# Flow_sensor.net
KiCad netlist of a schematic drawn in Altium Designer
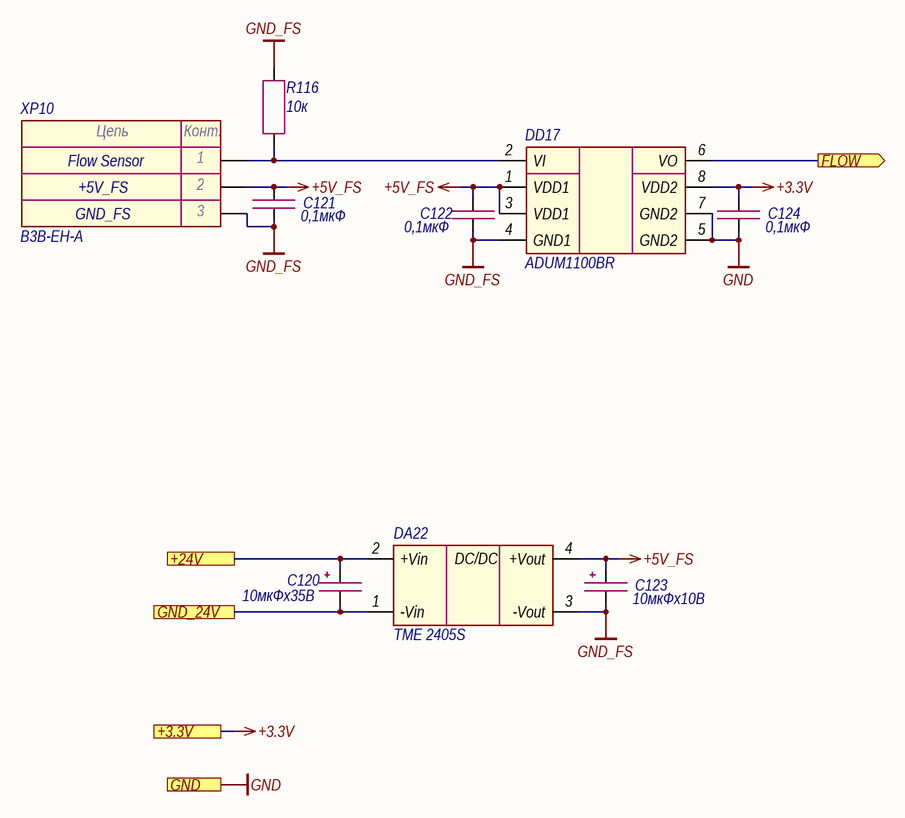
[diagram p0: Flow_sensor.SchDoc]

(export (version "E")
  (design (tool "Eeschema 10.0.6"))
  (components
    (comp (ref "C120")
      (value "10мкФх35B")
      (footprint "Pcb_library:CAP_C")
      (libsource (lib "Schem_library") (part "Capacitor_Polar"))
    )
    (comp (ref "C121")
      (value "0,1мкФ")
      (footprint "Pcb_library:CAP_0603")
      (fields (field (name "MANUFACTURER") "Murata"))
      (libsource (lib "Schem_library") (part "Capacitor"))
    )
    (comp (ref "C122")
      (value "0,1мкФ")
      (footprint "Pcb_library:CAP_0603")
      (fields (field (name "MANUFACTURER") "Murata"))
      (libsource (lib "Schem_library") (part "Capacitor"))
    )
    (comp (ref "C123")
      (value "10мкФх10B")
      (footprint "Pcb_library:CAP_A")
      (libsource (lib "Schem_library") (part "Capacitor_Polar"))
    )
    (comp (ref "C124")
      (value "0,1мкФ")
      (footprint "Pcb_library:CAP_0603")
      (fields (field (name "MANUFACTURER") "Murata"))
      (libsource (lib "Schem_library") (part "Capacitor"))
    )
    (comp (ref "DA22")
      (value "TME 2405S")
      (footprint "Pcb_library:TME (SIP-4)")
      (fields (field (name "MANUFACTURER") "Traco Power"))
      (libsource (lib "Schem_library") (part "TME"))
    )
    (comp (ref "DD17")
      (value "ADUM1100BR")
      (footprint "Pcb_library:SOIC-8")
      (fields (field (name "MANUFACTURER") "Analog Devices"))
      (libsource (lib "Schem_library") (part "ADUM1100"))
    )
    (comp (ref "R116")
      (value "10к")
      (footprint "Pcb_library:RES_0603")
      (fields (field (name "MANUFACTURER") "Yageo"))
      (libsource (lib "Schem_library") (part "Resistor"))
    )
    (comp (ref "XP10")
      (value "B3B-EH-A")
      (footprint "B3B-EH-A")
      (fields (field (name "MANUFACTURER") "JST"))
      (libsource (lib "Schem_library") (part "Connector-3"))
    )
  )
  (nets
    (net (code "1") (name "+3.3V") (class "Default")
      (node (ref "C124") (pin "1") (pinfunction "1_1") (pintype "passive"))
      (node (ref "DD17") (pin "8") (pinfunction "VDD2_8") (pintype "passive"))
    )
    (net (code "2") (name "+5V_FS") (class "Default")
      (node (ref "C121") (pin "1") (pinfunction "1_1") (pintype "passive"))
      (node (ref "C122") (pin "1") (pinfunction "1_1") (pintype "passive"))
      (node (ref "C123") (pin "1") (pinfunction "1_1") (pintype "passive"))
      (node (ref "DA22") (pin "4") (pinfunction "+Vout_4") (pintype "passive"))
      (node (ref "DD17") (pin "1") (pinfunction "VDD1_1") (pintype "passive"))
      (node (ref "DD17") (pin "3") (pinfunction "VDD1_3") (pintype "passive"))
      (node (ref "XP10") (pin "2") (pintype "passive"))
    )
    (net (code "3") (name "/+24V") (class "Default")
      (node (ref "C120") (pin "1") (pinfunction "1_1") (pintype "passive"))
      (node (ref "DA22") (pin "2") (pinfunction "+Vin_2") (pintype "passive"))
    )
    (net (code "4") (name "/FLOW") (class "Default")
      (node (ref "DD17") (pin "6") (pinfunction "VO_6") (pintype "passive"))
    )
    (net (code "5") (name "/GND_24V") (class "Default")
      (node (ref "C120") (pin "2") (pinfunction "2_2") (pintype "passive"))
      (node (ref "DA22") (pin "1") (pinfunction "-Vin_1") (pintype "passive"))
    )
    (net (code "6") (name "GND") (class "Default")
      (node (ref "C124") (pin "2") (pinfunction "2_2") (pintype "passive"))
      (node (ref "DD17") (pin "5") (pinfunction "GND2_5") (pintype "passive"))
      (node (ref "DD17") (pin "7") (pinfunction "GND2_7") (pintype "passive"))
    )
    (net (code "7") (name "GND_FS") (class "Default")
      (node (ref "C121") (pin "2") (pinfunction "2_2") (pintype "passive"))
      (node (ref "C122") (pin "2") (pinfunction "2_2") (pintype "passive"))
      (node (ref "C123") (pin "2") (pinfunction "2_2") (pintype "passive"))
      (node (ref "DA22") (pin "3") (pinfunction "-Vout_3") (pintype "passive"))
      (node (ref "DD17") (pin "4") (pinfunction "GND1_4") (pintype "passive"))
      (node (ref "R116") (pin "2") (pinfunction "2_2") (pintype "passive"))
      (node (ref "XP10") (pin "3") (pintype "passive"))
    )
    (net (code "8") (name "Net-(DD17-VI)") (class "Default")
      (node (ref "DD17") (pin "2") (pinfunction "VI_2") (pintype "passive"))
      (node (ref "R116") (pin "1") (pinfunction "1_1") (pintype "passive"))
      (node (ref "XP10") (pin "1") (pintype "passive"))
    )
  )
)
